# Adafruit_MCP73871_Solar_Charger_v4.net
KiCad netlist of a schematic drawn in EAGLE
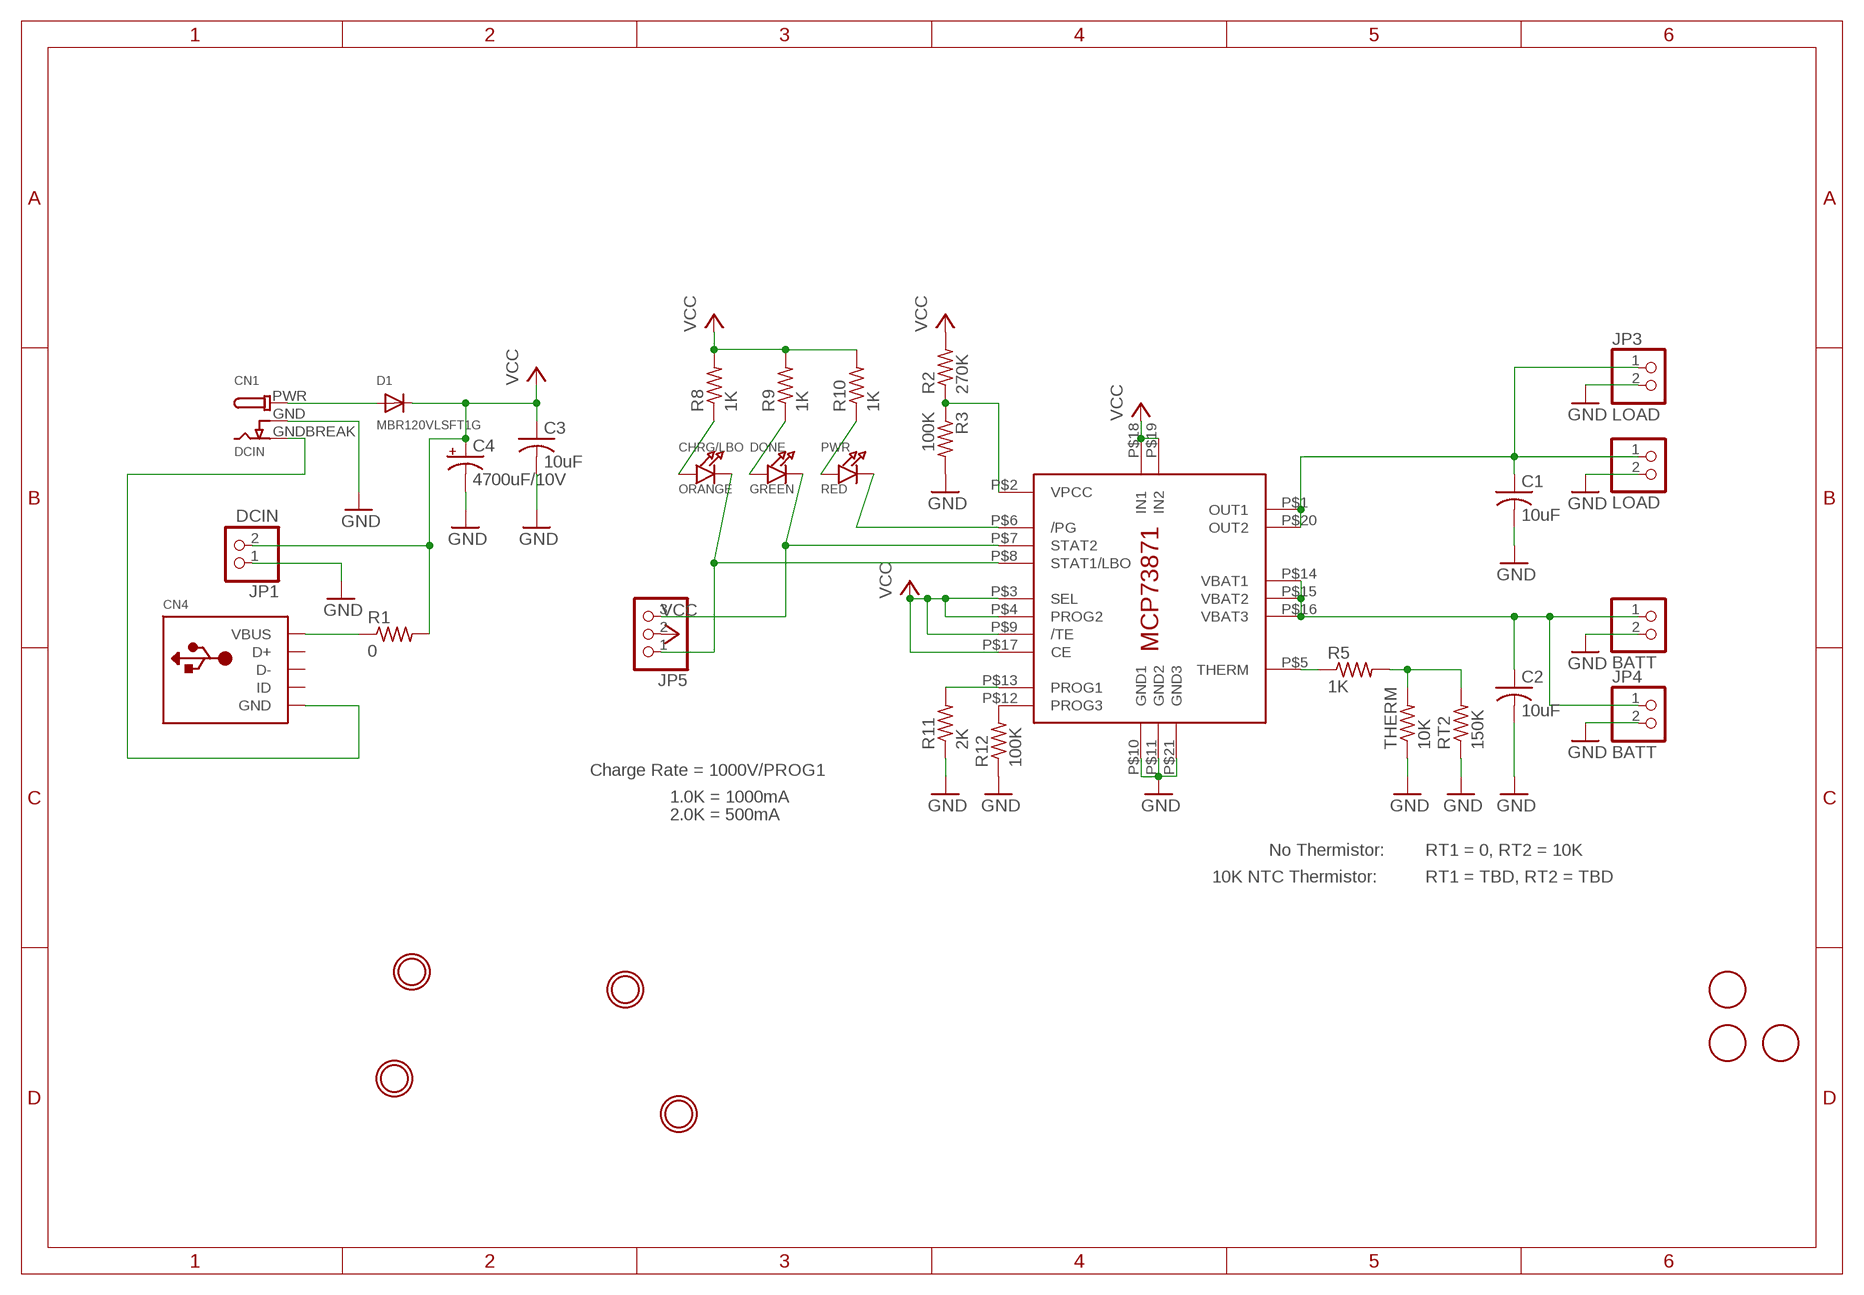
[diagram p0: schematic, sheet 1]

(export (version "E")
  (design (tool "Eeschema 10.0.6"))
  (components
    (comp (ref "BATT")
      (value "JST_2PIN-SMT-RA")
      (footprint "eagle-import:JST-PH-2-SMT-RA")
      (libsource (lib "eagle-import") (part "JST_2PIN-SMT-RA"))
    )
    (comp (ref "C1")
      (value "10uF")
      (footprint "eagle-import:C0805K")
      (libsource (lib "eagle-import") (part "C-USC0805K"))
    )
    (comp (ref "C2")
      (value "10uF")
      (footprint "eagle-import:C0805K")
      (libsource (lib "eagle-import") (part "C-USC0805K"))
    )
    (comp (ref "C3")
      (value "10uF")
      (footprint "eagle-import:C0805K")
      (libsource (lib "eagle-import") (part "C-USC0805K"))
    )
    (comp (ref "C4")
      (value "4700uF/10V")
      (footprint "eagle-import:E5-13")
      (libsource (lib "eagle-import") (part "CPOL-USE5-13"))
    )
    (comp (ref "CHRG/LBO")
      (value "ORANGE")
      (footprint "eagle-import:CHIPLED_0805_NOOUTLINE")
      (libsource (lib "eagle-import") (part "LED0805_NOOUTLINE"))
    )
    (comp (ref "CN1")
      (value "DCIN")
      (footprint "eagle-import:DCJACK_2MM_SMT")
      (libsource (lib "eagle-import") (part "DCBARRELSMT"))
    )
    (comp (ref "CN4")
      (value "USBMINIBLARGE")
      (footprint "eagle-import:USB-MINIB_LARGER")
      (libsource (lib "eagle-import") (part "USBMINIBLARGE"))
    )
    (comp (ref "D1")
      (value "MBR120VLSFT1G")
      (footprint "eagle-import:SOD-123")
      (libsource (lib "eagle-import") (part "DIODESOD-123"))
    )
    (comp (ref "DONE")
      (value "GREEN")
      (footprint "eagle-import:CHIPLED_0805_NOOUTLINE")
      (libsource (lib "eagle-import") (part "LED0805_NOOUTLINE"))
    )
    (comp (ref "IC1")
      (value "MCP73871")
      (footprint "eagle-import:QFN20_4MM")
      (libsource (lib "eagle-import") (part "MCP73871"))
    )
    (comp (ref "JP1")
      (value "DCIN")
      (footprint "eagle-import:1X02_OVAL")
      (libsource (lib "eagle-import") (part "HEADER-1X2"))
    )
    (comp (ref "JP3")
      (value "LOAD")
      (footprint "eagle-import:1X02_ROUND")
      (libsource (lib "eagle-import") (part "HEADER-1X2ROUND"))
    )
    (comp (ref "JP4")
      (value "BATT")
      (footprint "eagle-import:1X02_ROUND")
      (libsource (lib "eagle-import") (part "HEADER-1X2ROUND"))
    )
    (comp (ref "JP5")
      (value "PINHD-1X3CB")
      (footprint "eagle-import:1X03-CLEANBIG")
      (libsource (lib "eagle-import") (part "PINHD-1X3CB"))
    )
    (comp (ref "LOAD")
      (value "JST_2PIN-SMT-RA")
      (footprint "eagle-import:JST-PH-2-SMT-RA")
      (libsource (lib "eagle-import") (part "JST_2PIN-SMT-RA"))
    )
    (comp (ref "PWR")
      (value "RED")
      (footprint "eagle-import:CHIPLED_0805_NOOUTLINE")
      (libsource (lib "eagle-import") (part "LED0805_NOOUTLINE"))
    )
    (comp (ref "R1")
      (value "0")
      (footprint "eagle-import:R0805")
      (libsource (lib "eagle-import") (part "R-US_R0805"))
    )
    (comp (ref "R2")
      (value "270K")
      (footprint "eagle-import:R0805")
      (libsource (lib "eagle-import") (part "R-US_R0805"))
    )
    (comp (ref "R3")
      (value "100K")
      (footprint "eagle-import:R0805")
      (libsource (lib "eagle-import") (part "R-US_R0805"))
    )
    (comp (ref "R5")
      (value "1K")
      (footprint "eagle-import:M0805")
      (libsource (lib "eagle-import") (part "R-US_M0805"))
    )
    (comp (ref "R8")
      (value "1K")
      (footprint "eagle-import:R0805")
      (libsource (lib "eagle-import") (part "R-US_R0805"))
    )
    (comp (ref "R9")
      (value "1K")
      (footprint "eagle-import:R0805")
      (libsource (lib "eagle-import") (part "R-US_R0805"))
    )
    (comp (ref "R10")
      (value "1K")
      (footprint "eagle-import:R0805")
      (libsource (lib "eagle-import") (part "R-US_R0805"))
    )
    (comp (ref "R11")
      (value "2K")
      (footprint "eagle-import:0805-THM")
      (libsource (lib "eagle-import") (part "R-US_FLIPFLOP"))
    )
    (comp (ref "R12")
      (value "100K")
      (footprint "eagle-import:R0805")
      (libsource (lib "eagle-import") (part "R-US_R0805"))
    )
    (comp (ref "RT2")
      (value "150K")
      (footprint "eagle-import:M0805")
      (libsource (lib "eagle-import") (part "R-US_M0805"))
    )
    (comp (ref "THERM")
      (value "10K")
      (footprint "eagle-import:0805-THM")
      (libsource (lib "eagle-import") (part "R-US_FLIPFLOP"))
    )
    (comp (ref "U$2")
      (value "FIDUCIAL")
      (footprint "eagle-import:FIDUCIAL_1MM")
      (libsource (lib "eagle-import") (part "FIDUCIAL"))
    )
    (comp (ref "U$3")
      (value "FIDUCIAL")
      (footprint "eagle-import:FIDUCIAL_1MM")
      (libsource (lib "eagle-import") (part "FIDUCIAL"))
    )
    (comp (ref "U$4")
      (value "MOUNTINGHOLE2.5")
      (footprint "eagle-import:MOUNTINGHOLE_2.5_PLATED")
      (libsource (lib "eagle-import") (part "MOUNTINGHOLE2.5"))
    )
    (comp (ref "U$5")
      (value "MOUNTINGHOLE2.5")
      (footprint "eagle-import:MOUNTINGHOLE_2.5_PLATED")
      (libsource (lib "eagle-import") (part "MOUNTINGHOLE2.5"))
    )
    (comp (ref "U$6")
      (value "MOUNTINGHOLE2.5")
      (footprint "eagle-import:MOUNTINGHOLE_2.5_PLATED")
      (libsource (lib "eagle-import") (part "MOUNTINGHOLE2.5"))
    )
    (comp (ref "U$7")
      (value "MOUNTINGHOLE2.5")
      (footprint "eagle-import:MOUNTINGHOLE_2.5_PLATED")
      (libsource (lib "eagle-import") (part "MOUNTINGHOLE2.5"))
    )
    (comp (ref "U$8")
      (value "FIDUCIAL")
      (footprint "eagle-import:FIDUCIAL_1MM")
      (libsource (lib "eagle-import") (part "FIDUCIAL"))
    )
  )
  (nets
    (net (code "1") (name "GND") (class "Default")
      (node (ref "BATT") (pin "2") (pinfunction "1_2") (pintype "passive"))
      (node (ref "C1") (pin "2") (pinfunction "2_2") (pintype "passive"))
      (node (ref "C2") (pin "2") (pinfunction "2_2") (pintype "passive"))
      (node (ref "C3") (pin "2") (pinfunction "2_2") (pintype "passive"))
      (node (ref "C4") (pin "-") (pinfunction "-_-") (pintype "passive"))
      (node (ref "CN1") (pin "GND") (pinfunction "GNDBREAK_GND") (pintype "power_in"))
      (node (ref "IC1") (pin "P$10") (pinfunction "GND1_P$10") (pintype "power_in"))
      (node (ref "IC1") (pin "P$11") (pinfunction "GND2_P$11") (pintype "power_in"))
      (node (ref "IC1") (pin "P$21") (pinfunction "GND3_P$21") (pintype "power_in"))
      (node (ref "JP1") (pin "1") (pinfunction "1_1") (pintype "passive"))
      (node (ref "JP3") (pin "2") (pinfunction "2_2") (pintype "passive"))
      (node (ref "JP4") (pin "2") (pinfunction "2_2") (pintype "passive"))
      (node (ref "LOAD") (pin "2") (pinfunction "1_2") (pintype "passive"))
      (node (ref "R11") (pin "1") (pinfunction "1_1") (pintype "passive"))
      (node (ref "R12") (pin "1") (pinfunction "1_1") (pintype "passive"))
      (node (ref "R3") (pin "2") (pinfunction "2_2") (pintype "passive"))
      (node (ref "RT2") (pin "1") (pinfunction "1_1") (pintype "passive"))
      (node (ref "THERM") (pin "1") (pinfunction "1_1") (pintype "passive"))
    )
    (net (code "2") (name "Net-(BATT-2)") (class "Default")
      (node (ref "BATT") (pin "1") (pinfunction "2_1") (pintype "passive"))
      (node (ref "C2") (pin "1") (pinfunction "1_1") (pintype "passive"))
      (node (ref "IC1") (pin "P$14") (pinfunction "VBAT1_P$14") (pintype "output"))
      (node (ref "IC1") (pin "P$15") (pinfunction "VBAT2_P$15") (pintype "output"))
      (node (ref "IC1") (pin "P$16") (pinfunction "VBAT3_P$16") (pintype "output"))
      (node (ref "JP4") (pin "1") (pinfunction "1_1") (pintype "passive"))
    )
    (net (code "3") (name "Net-(CHRG/LBO-PadA)") (class "Default")
      (node (ref "CHRG/LBO") (pin "A") (pinfunction "A_A") (pintype "passive"))
      (node (ref "R8") (pin "1") (pinfunction "1_1") (pintype "passive"))
    )
    (net (code "4") (name "Net-(CN1-GND)") (class "Default")
      (node (ref "CN1") (pin "GNDBREAK") (pinfunction "GND_GNDBREAK") (pintype "power_in"))
      (node (ref "CN4") (pin "GND") (pinfunction "GND_GND") (pintype "power_in"))
      (node (ref "CN4") (pin "GND1") (pinfunction "GND_GND1") (pintype "power_in"))
      (node (ref "CN4") (pin "GND2") (pinfunction "GND_GND2") (pintype "power_in"))
      (node (ref "CN4") (pin "GND3") (pinfunction "GND_GND3") (pintype "power_in"))
      (node (ref "CN4") (pin "GND4") (pinfunction "GND_GND4") (pintype "power_in"))
    )
    (net (code "5") (name "Net-(CN1-PadPWR)") (class "Default")
      (node (ref "CN1") (pin "PWR") (pinfunction "PWR_PWR") (pintype "power_in"))
      (node (ref "D1") (pin "A") (pinfunction "A_A") (pintype "passive"))
    )
    (net (code "6") (name "Net-(CN4-PadVBUS)") (class "Default")
      (node (ref "CN4") (pin "VBUS") (pinfunction "VBUS_VBUS") (pintype "power_in"))
      (node (ref "R1") (pin "1") (pinfunction "1_1") (pintype "passive"))
    )
    (net (code "7") (name "Net-(DONE-PadA)") (class "Default")
      (node (ref "DONE") (pin "A") (pinfunction "A_A") (pintype "passive"))
      (node (ref "R9") (pin "1") (pinfunction "1_1") (pintype "passive"))
    )
    (net (code "8") (name "Net-(IC1-OUT1)") (class "Default")
      (node (ref "C1") (pin "1") (pinfunction "1_1") (pintype "passive"))
      (node (ref "IC1") (pin "P$1") (pinfunction "OUT1_P$1") (pintype "output"))
      (node (ref "IC1") (pin "P$20") (pinfunction "OUT2_P$20") (pintype "output"))
      (node (ref "JP3") (pin "1") (pinfunction "1_1") (pintype "passive"))
      (node (ref "LOAD") (pin "1") (pinfunction "2_1") (pintype "passive"))
    )
    (net (code "9") (name "Net-(IC1-PROG1)") (class "Default")
      (node (ref "IC1") (pin "P$13") (pinfunction "PROG1_P$13") (pintype "input"))
      (node (ref "R11") (pin "2") (pinfunction "2_2") (pintype "passive"))
    )
    (net (code "10") (name "Net-(IC1-PROG3)") (class "Default")
      (node (ref "IC1") (pin "P$12") (pinfunction "PROG3_P$12") (pintype "input"))
      (node (ref "R12") (pin "2") (pinfunction "2_2") (pintype "passive"))
    )
    (net (code "11") (name "Net-(IC1-STAT1{slash}LBO)") (class "Default")
      (node (ref "CHRG/LBO") (pin "C") (pinfunction "C_C") (pintype "passive"))
      (node (ref "IC1") (pin "P$8") (pinfunction "STAT1/LBO_P$8") (pintype "output"))
      (node (ref "JP5") (pin "1") (pinfunction "1_1") (pintype "passive"))
    )
    (net (code "12") (name "Net-(IC1-STAT2)") (class "Default")
      (node (ref "DONE") (pin "C") (pinfunction "C_C") (pintype "passive"))
      (node (ref "IC1") (pin "P$7") (pinfunction "STAT2_P$7") (pintype "output"))
      (node (ref "JP5") (pin "3") (pinfunction "3_3") (pintype "passive"))
    )
    (net (code "13") (name "Net-(IC1-THERM)") (class "Default")
      (node (ref "IC1") (pin "P$5") (pinfunction "THERM_P$5") (pintype "input"))
      (node (ref "R5") (pin "1") (pinfunction "1_1") (pintype "passive"))
    )
    (net (code "14") (name "Net-(IC1-VPCC)") (class "Default")
      (node (ref "IC1") (pin "P$2") (pinfunction "VPCC_P$2") (pintype "input"))
      (node (ref "R2") (pin "1") (pinfunction "1_1") (pintype "passive"))
      (node (ref "R3") (pin "1") (pinfunction "1_1") (pintype "passive"))
    )
    (net (code "15") (name "Net-(IC1-{slash}PG)") (class "Default")
      (node (ref "IC1") (pin "P$6") (pinfunction "/PG_P$6") (pintype "output"))
      (node (ref "PWR") (pin "C") (pinfunction "C_C") (pintype "passive"))
    )
    (net (code "16") (name "Net-(PWR-PadA)") (class "Default")
      (node (ref "PWR") (pin "A") (pinfunction "A_A") (pintype "passive"))
      (node (ref "R10") (pin "1") (pinfunction "1_1") (pintype "passive"))
    )
    (net (code "17") (name "Net-(R5-Pad2)") (class "Default")
      (node (ref "R5") (pin "2") (pinfunction "2_2") (pintype "passive"))
      (node (ref "RT2") (pin "2") (pinfunction "2_2") (pintype "passive"))
      (node (ref "THERM") (pin "2") (pinfunction "2_2") (pintype "passive"))
    )
    (net (code "18") (name "VCC") (class "Default")
      (node (ref "C3") (pin "1") (pinfunction "1_1") (pintype "passive"))
      (node (ref "C4") (pin "+") (pinfunction "+_+") (pintype "passive"))
      (node (ref "D1") (pin "C") (pinfunction "C_C") (pintype "passive"))
      (node (ref "IC1") (pin "P$17") (pinfunction "CE_P$17") (pintype "input"))
      (node (ref "IC1") (pin "P$18") (pinfunction "IN1_P$18") (pintype "input"))
      (node (ref "IC1") (pin "P$19") (pinfunction "IN2_P$19") (pintype "input"))
      (node (ref "IC1") (pin "P$3") (pinfunction "SEL_P$3") (pintype "input"))
      (node (ref "IC1") (pin "P$4") (pinfunction "PROG2_P$4") (pintype "input"))
      (node (ref "IC1") (pin "P$9") (pinfunction "/TE_P$9") (pintype "input"))
      (node (ref "JP1") (pin "2") (pinfunction "2_2") (pintype "passive"))
      (node (ref "JP5") (pin "2") (pinfunction "2_2") (pintype "passive"))
      (node (ref "R1") (pin "2") (pinfunction "2_2") (pintype "passive"))
      (node (ref "R10") (pin "2") (pinfunction "2_2") (pintype "passive"))
      (node (ref "R2") (pin "2") (pinfunction "2_2") (pintype "passive"))
      (node (ref "R8") (pin "2") (pinfunction "2_2") (pintype "passive"))
      (node (ref "R9") (pin "2") (pinfunction "2_2") (pintype "passive"))
    )
    (net (code "19") (name "unconnected-(CN4-PadD+)") (class "Default")
      (node (ref "CN4") (pin "D+") (pinfunction "D+_D+") (pintype "bidirectional"))
    )
    (net (code "20") (name "unconnected-(CN4-PadD-)") (class "Default")
      (node (ref "CN4") (pin "D-") (pinfunction "D-_D-") (pintype "bidirectional"))
    )
    (net (code "21") (name "unconnected-(CN4-PadID)") (class "Default")
      (node (ref "CN4") (pin "ID") (pinfunction "ID_ID") (pintype "bidirectional"))
    )
  )
)
